# 1_MCU_and_BLE.net
KiCad netlist of a schematic drawn in Altium Designer
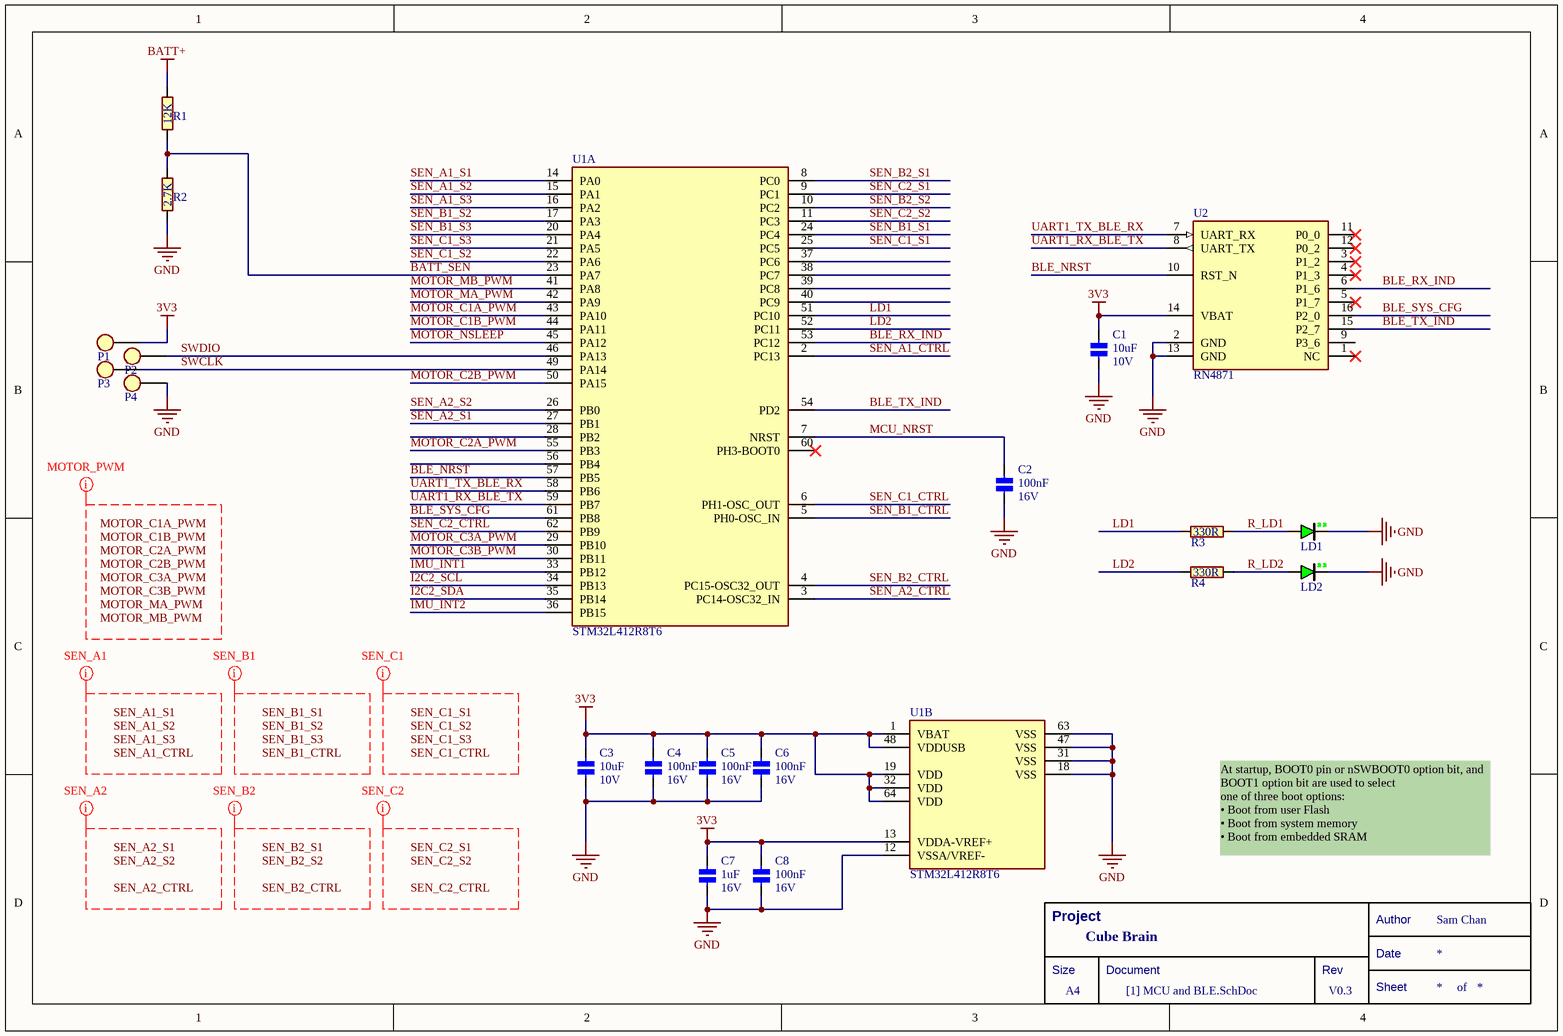
[diagram p0: [1] MCU and BLE.SchDoc]

(export (version "E")
  (design (tool "Eeschema 10.0.6"))
  (components
    (comp (ref "C1")
      (value "10uF")
      (footprint "CAPC0402X05N")
      (description "CAP CER 10UF 10V X5R 0402")
      (fields
        (field (name "MANUFACTURER") "Murata Electronics")
        (field (name "MANUFACTURER PART NUMBER") "GRM155R61A106ME44D")
        (field (name "CAPACITANCE") "10uF")
        (field (name "VOLTAGE - RATED") "10V")
      )
      (libsource (lib "Cube Library") (part "CER 10UF 10V"))
    )
    (comp (ref "C2")
      (value "100nF")
      (footprint "CAPC0402X05N")
      (description "CAP CER 0.1UF 16V X7R 0402")
      (fields
        (field (name "MANUFACTURER") "Samsung Electro-Mechanics")
        (field (name "MANUFACTURER PART NUMBER") "CL05B104KO5NNNC")
        (field (name "CAPACITANCE") "100nF")
        (field (name "VOLTAGE - RATED") "16V")
      )
      (libsource (lib "Cube Library") (part "CER 100NF 16V"))
    )
    (comp (ref "C3")
      (value "10uF")
      (footprint "CAPC0402X05N")
      (description "CAP CER 10UF 10V X5R 0402")
      (fields
        (field (name "MANUFACTURER") "Murata Electronics")
        (field (name "MANUFACTURER PART NUMBER") "GRM155R61A106ME44D")
        (field (name "CAPACITANCE") "10uF")
        (field (name "VOLTAGE - RATED") "10V")
      )
      (libsource (lib "Cube Library") (part "CER 10UF 10V"))
    )
    (comp (ref "C4")
      (value "100nF")
      (footprint "CAPC0402X05N")
      (description "CAP CER 0.1UF 16V X7R 0402")
      (fields
        (field (name "MANUFACTURER") "Samsung Electro-Mechanics")
        (field (name "MANUFACTURER PART NUMBER") "CL05B104KO5NNNC")
        (field (name "CAPACITANCE") "100nF")
        (field (name "VOLTAGE - RATED") "16V")
      )
      (libsource (lib "Cube Library") (part "CER 100NF 16V"))
    )
    (comp (ref "C5")
      (value "100nF")
      (footprint "CAPC0402X05N")
      (description "CAP CER 0.1UF 16V X7R 0402")
      (fields
        (field (name "MANUFACTURER") "Samsung Electro-Mechanics")
        (field (name "MANUFACTURER PART NUMBER") "CL05B104KO5NNNC")
        (field (name "CAPACITANCE") "100nF")
        (field (name "VOLTAGE - RATED") "16V")
      )
      (libsource (lib "Cube Library") (part "CER 100NF 16V"))
    )
    (comp (ref "C6")
      (value "100nF")
      (footprint "CAPC0402X05N")
      (description "CAP CER 0.1UF 16V X7R 0402")
      (fields
        (field (name "MANUFACTURER") "Samsung Electro-Mechanics")
        (field (name "MANUFACTURER PART NUMBER") "CL05B104KO5NNNC")
        (field (name "CAPACITANCE") "100nF")
        (field (name "VOLTAGE - RATED") "16V")
      )
      (libsource (lib "Cube Library") (part "CER 100NF 16V"))
    )
    (comp (ref "C7")
      (value "1uF")
      (footprint "CAPC0402X05N")
      (description "CAP CER 1UF 16V X5R 0402")
      (fields
        (field (name "MANUFACTURER") "Samsung Electro-Mechanics")
        (field (name "MANUFACTURER PART NUMBER") "CL05A105KO5NNNC")
        (field (name "CAPACITANCE") "1uF")
        (field (name "VOLTAGE - RATED") "16V")
      )
      (libsource (lib "Cube Library") (part "CER 1UF 16V"))
    )
    (comp (ref "C8")
      (value "100nF")
      (footprint "CAPC0402X05N")
      (description "CAP CER 0.1UF 16V X7R 0402")
      (fields
        (field (name "MANUFACTURER") "Samsung Electro-Mechanics")
        (field (name "MANUFACTURER PART NUMBER") "CL05B104KO5NNNC")
        (field (name "CAPACITANCE") "100nF")
        (field (name "VOLTAGE - RATED") "16V")
      )
      (libsource (lib "Cube Library") (part "CER 100NF 16V"))
    )
    (comp (ref "LD1")
      (value "Green")
      (footprint "LEDM0603X08N_GREEN")
      (description "LED GREEN CLEAR CHIP SMD")
      (fields
        (field (name "MANUFACTURER") "Lite-On Inc.")
        (field (name "MANUFACTURER PART NUMBER") "LTST-C190KGKT")
      )
      (libsource (lib "Cube Library") (part "LED 0603 GREEN"))
    )
    (comp (ref "LD2")
      (value "Green")
      (footprint "LEDM0603X08N_GREEN")
      (description "LED GREEN CLEAR CHIP SMD")
      (fields
        (field (name "MANUFACTURER") "Lite-On Inc.")
        (field (name "MANUFACTURER PART NUMBER") "LTST-C190KGKT")
      )
      (libsource (lib "Cube Library") (part "LED 0603 GREEN"))
    )
    (comp (ref "P1")
      (value "PAD_3")
      (footprint "Cube:PAD_ROUND_1MM")
      (description "a Round Pad 1mm")
      (libsource (lib "Cube") (part "PAD_3"))
    )
    (comp (ref "P2")
      (value "PAD_3")
      (footprint "Cube:PAD_ROUND_1MM")
      (description "a Round Pad 1mm")
      (libsource (lib "Cube") (part "PAD_3"))
    )
    (comp (ref "P3")
      (value "PAD_3")
      (footprint "Cube:PAD_ROUND_1MM")
      (description "a Round Pad 1mm")
      (libsource (lib "Cube") (part "PAD_3"))
    )
    (comp (ref "P4")
      (value "PAD_3")
      (footprint "Cube:PAD_ROUND_1MM")
      (description "a Round Pad 1mm")
      (libsource (lib "Cube") (part "PAD_3"))
    )
    (comp (ref "R1")
      (value "12K")
      (footprint "RESC0402X04N")
      (description "RES SMD 12K OHM 1% 1/16W 0402")
      (fields
        (field (name "MANUFACTURER") "YAGEO")
        (field (name "MANUFACTURER PART NUMBER") "RC0402FR-0712KL")
        (field (name "RESISTANCE") "12K")
      )
      (libsource (lib "Cube Library") (part "RES 12K"))
    )
    (comp (ref "R2")
      (value "2.7K")
      (footprint "RESC0402X04N")
      (description "RES SMD 2.7K OHM 1% 1/16W 0402")
      (fields
        (field (name "MANUFACTURER") "YAGEO")
        (field (name "MANUFACTURER PART NUMBER") "AC0402FR-072K7L")
        (field (name "RESISTANCE") "2.7K")
      )
      (libsource (lib "Cube Library") (part "RES 2.7K"))
    )
    (comp (ref "R3")
      (value "330R")
      (footprint "RESC0402X04N")
      (description "RES SMD 330R OHM 1% 1/16W 0402")
      (fields
        (field (name "MANUFACTURER") "YAGEO")
        (field (name "MANUFACTURER PART NUMBER") "RC0402FR-07330RL")
        (field (name "RESISTANCE") "330R")
      )
      (libsource (lib "Cube Library") (part "RES 330R"))
    )
    (comp (ref "R4")
      (value "330R")
      (footprint "RESC0402X04N")
      (description "RES SMD 330R OHM 1% 1/16W 0402")
      (fields
        (field (name "MANUFACTURER") "YAGEO")
        (field (name "MANUFACTURER PART NUMBER") "RC0402FR-07330RL")
        (field (name "RESISTANCE") "330R")
      )
      (libsource (lib "Cube Library") (part "RES 330R"))
    )
    (comp (ref "U1")
      (value "STM32L412R8T6")
      (footprint "STM32L412R")
      (description "ARM® Cortex®-M4 STM32L4 Microcontroller IC 32-Bit 80MHz 64KB (64K x 8) FLASH 64-LQFP (10x10)")
      (fields (field (name "MANUFACTURER") "STMicroelectronics"))
      (libsource (lib "Cube Library") (part "STM32L412R8T6"))
    )
    (comp (ref "U2")
      (value "RN4871")
      (footprint "RN4871")
      (description "Bluetooth Bluetooth v5.0 Transceiver Module 2.4GHz Integrated, Chip Surface Mount")
      (fields
        (field (name "MANUFACTURER") "Microchip Technology")
        (field (name "MANUFACTURER PART NUMBER") "RN4871-I/RM130")
      )
      (libsource (lib "Cube Library") (part "RN4871"))
    )
  )
  (nets
    (net (code "1") (name "/BATT_SEN") (class "Default")
      (node (ref "R1") (pin "1") (pinfunction "1_1") (pintype "passive"))
      (node (ref "R2") (pin "2") (pinfunction "2_2") (pintype "passive"))
      (node (ref "U1") (pin "23") (pinfunction "PA7_23") (pintype "passive"))
    )
    (net (code "2") (name "/BLE_NRST") (class "Default")
      (node (ref "U1") (pin "57") (pinfunction "PB5_57") (pintype "passive"))
      (node (ref "U2") (pin "10") (pinfunction "RST_N_10") (pintype "passive"))
    )
    (net (code "3") (name "/BLE_RX_IND") (class "Default")
      (node (ref "U1") (pin "53") (pinfunction "PC12_53") (pintype "passive"))
      (node (ref "U2") (pin "6") (pinfunction "P1_6_6") (pintype "passive"))
    )
    (net (code "4") (name "/BLE_SYS_CFG") (class "Default")
      (node (ref "U1") (pin "61") (pinfunction "PB8_61") (pintype "passive"))
      (node (ref "U2") (pin "16") (pinfunction "P2_0_16") (pintype "passive"))
    )
    (net (code "5") (name "/BLE_TX_IND") (class "Default")
      (node (ref "U1") (pin "54") (pinfunction "PD2_54") (pintype "passive"))
      (node (ref "U2") (pin "15") (pinfunction "P2_7_15") (pintype "passive"))
    )
    (net (code "6") (name "/I2C2_SCL") (class "Default")
      (node (ref "U1") (pin "34") (pinfunction "PB13_34") (pintype "passive"))
    )
    (net (code "7") (name "/I2C2_SDA") (class "Default")
      (node (ref "U1") (pin "35") (pinfunction "PB14_35") (pintype "passive"))
    )
    (net (code "8") (name "/IMU_INT1") (class "Default")
      (node (ref "U1") (pin "33") (pinfunction "PB12_33") (pintype "passive"))
    )
    (net (code "9") (name "/IMU_INT2") (class "Default")
      (node (ref "U1") (pin "36") (pinfunction "PB15_36") (pintype "passive"))
    )
    (net (code "10") (name "/LD1") (class "Default")
      (node (ref "R3") (pin "1") (pinfunction "1_1") (pintype "passive"))
      (node (ref "U1") (pin "51") (pinfunction "PC10_51") (pintype "passive"))
    )
    (net (code "11") (name "/LD2") (class "Default")
      (node (ref "R4") (pin "1") (pinfunction "1_1") (pintype "passive"))
      (node (ref "U1") (pin "52") (pinfunction "PC11_52") (pintype "passive"))
    )
    (net (code "12") (name "/MCU_NRST") (class "Default")
      (node (ref "C2") (pin "1") (pinfunction "1_1") (pintype "passive"))
      (node (ref "U1") (pin "7") (pinfunction "NRST_7") (pintype "passive"))
    )
    (net (code "13") (name "/MOTOR_C1A_PWM") (class "Default")
      (node (ref "U1") (pin "43") (pinfunction "PA10_43") (pintype "passive"))
    )
    (net (code "14") (name "/MOTOR_C1B_PWM") (class "Default")
      (node (ref "U1") (pin "44") (pinfunction "PA11_44") (pintype "passive"))
    )
    (net (code "15") (name "/MOTOR_C2A_PWM") (class "Default")
      (node (ref "U1") (pin "55") (pinfunction "PB3_55") (pintype "passive"))
    )
    (net (code "16") (name "/MOTOR_C2B_PWM") (class "Default")
      (node (ref "U1") (pin "50") (pinfunction "PA15_50") (pintype "passive"))
    )
    (net (code "17") (name "/MOTOR_C3A_PWM") (class "Default")
      (node (ref "U1") (pin "29") (pinfunction "PB10_29") (pintype "passive"))
    )
    (net (code "18") (name "/MOTOR_C3B_PWM") (class "Default")
      (node (ref "U1") (pin "30") (pinfunction "PB11_30") (pintype "passive"))
    )
    (net (code "19") (name "/MOTOR_MA_PWM") (class "Default")
      (node (ref "U1") (pin "42") (pinfunction "PA9_42") (pintype "passive"))
    )
    (net (code "20") (name "/MOTOR_MB_PWM") (class "Default")
      (node (ref "U1") (pin "41") (pinfunction "PA8_41") (pintype "passive"))
    )
    (net (code "21") (name "/MOTOR_NSLEEP") (class "Default")
      (node (ref "U1") (pin "45") (pinfunction "PA12_45") (pintype "passive"))
    )
    (net (code "22") (name "/R_LD1") (class "Default")
      (node (ref "LD1") (pin "1") (pinfunction "1_1") (pintype "passive"))
      (node (ref "R3") (pin "2") (pinfunction "2_2") (pintype "passive"))
    )
    (net (code "23") (name "/R_LD2") (class "Default")
      (node (ref "LD2") (pin "1") (pinfunction "1_1") (pintype "passive"))
      (node (ref "R4") (pin "2") (pinfunction "2_2") (pintype "passive"))
    )
    (net (code "24") (name "/SEN_A1_CTRL") (class "Default")
      (node (ref "U1") (pin "2") (pinfunction "PC13_2") (pintype "passive"))
    )
    (net (code "25") (name "/SEN_A1_S1") (class "Default")
      (node (ref "U1") (pin "14") (pinfunction "PA0_14") (pintype "passive"))
    )
    (net (code "26") (name "/SEN_A1_S2") (class "Default")
      (node (ref "U1") (pin "15") (pinfunction "PA1_15") (pintype "passive"))
    )
    (net (code "27") (name "/SEN_A1_S3") (class "Default")
      (node (ref "U1") (pin "16") (pinfunction "PA2_16") (pintype "passive"))
    )
    (net (code "28") (name "/SEN_A2_CTRL") (class "Default")
      (node (ref "U1") (pin "3") (pinfunction "PC14-OSC32_IN_3") (pintype "passive"))
    )
    (net (code "29") (name "/SEN_A2_S1") (class "Default")
      (node (ref "U1") (pin "27") (pinfunction "PB1_27") (pintype "passive"))
    )
    (net (code "30") (name "/SEN_A2_S2") (class "Default")
      (node (ref "U1") (pin "26") (pinfunction "PB0_26") (pintype "passive"))
    )
    (net (code "31") (name "/SEN_B1_CTRL") (class "Default")
      (node (ref "U1") (pin "5") (pinfunction "PH0-OSC_IN_5") (pintype "passive"))
    )
    (net (code "32") (name "/SEN_B1_S1") (class "Default")
      (node (ref "U1") (pin "24") (pinfunction "PC4_24") (pintype "passive"))
    )
    (net (code "33") (name "/SEN_B1_S2") (class "Default")
      (node (ref "U1") (pin "17") (pinfunction "PA3_17") (pintype "passive"))
    )
    (net (code "34") (name "/SEN_B1_S3") (class "Default")
      (node (ref "U1") (pin "20") (pinfunction "PA4_20") (pintype "passive"))
    )
    (net (code "35") (name "/SEN_B2_CTRL") (class "Default")
      (node (ref "U1") (pin "4") (pinfunction "PC15-OSC32_OUT_4") (pintype "passive"))
    )
    (net (code "36") (name "/SEN_B2_S1") (class "Default")
      (node (ref "U1") (pin "8") (pinfunction "PC0_8") (pintype "passive"))
    )
    (net (code "37") (name "/SEN_B2_S2") (class "Default")
      (node (ref "U1") (pin "10") (pinfunction "PC2_10") (pintype "passive"))
    )
    (net (code "38") (name "/SEN_C1_CTRL") (class "Default")
      (node (ref "U1") (pin "6") (pinfunction "PH1-OSC_OUT_6") (pintype "passive"))
    )
    (net (code "39") (name "/SEN_C1_S1") (class "Default")
      (node (ref "U1") (pin "25") (pinfunction "PC5_25") (pintype "passive"))
    )
    (net (code "40") (name "/SEN_C1_S2") (class "Default")
      (node (ref "U1") (pin "22") (pinfunction "PA6_22") (pintype "passive"))
    )
    (net (code "41") (name "/SEN_C1_S3") (class "Default")
      (node (ref "U1") (pin "21") (pinfunction "PA5_21") (pintype "passive"))
    )
    (net (code "42") (name "/SEN_C2_CTRL") (class "Default")
      (node (ref "U1") (pin "62") (pinfunction "PB9_62") (pintype "passive"))
    )
    (net (code "43") (name "/SEN_C2_S1") (class "Default")
      (node (ref "U1") (pin "9") (pinfunction "PC1_9") (pintype "passive"))
    )
    (net (code "44") (name "/SEN_C2_S2") (class "Default")
      (node (ref "U1") (pin "11") (pinfunction "PC3_11") (pintype "passive"))
    )
    (net (code "45") (name "/SWCLK") (class "Default")
      (node (ref "P3") (pin "1") (pinfunction "1_1") (pintype "passive"))
      (node (ref "U1") (pin "49") (pinfunction "PA14_49") (pintype "passive"))
    )
    (net (code "46") (name "/SWDIO") (class "Default")
      (node (ref "P2") (pin "1") (pinfunction "1_1") (pintype "passive"))
      (node (ref "U1") (pin "46") (pinfunction "PA13_46") (pintype "passive"))
    )
    (net (code "47") (name "/UART1_RX_BLE_TX") (class "Default")
      (node (ref "U1") (pin "59") (pinfunction "PB7_59") (pintype "passive"))
      (node (ref "U2") (pin "8") (pinfunction "UART_TX_8") (pintype "output"))
    )
    (net (code "48") (name "/UART1_TX_BLE_RX") (class "Default")
      (node (ref "U1") (pin "58") (pinfunction "PB6_58") (pintype "passive"))
      (node (ref "U2") (pin "7") (pinfunction "UART_RX_7") (pintype "input"))
    )
    (net (code "49") (name "3V3") (class "Default")
      (node (ref "C1") (pin "1") (pinfunction "1_1") (pintype "passive"))
      (node (ref "C3") (pin "1") (pinfunction "1_1") (pintype "passive"))
      (node (ref "C4") (pin "1") (pinfunction "1_1") (pintype "passive"))
      (node (ref "C5") (pin "1") (pinfunction "1_1") (pintype "passive"))
      (node (ref "C6") (pin "1") (pinfunction "1_1") (pintype "passive"))
      (node (ref "C7") (pin "1") (pinfunction "1_1") (pintype "passive"))
      (node (ref "C8") (pin "1") (pinfunction "1_1") (pintype "passive"))
      (node (ref "P1") (pin "1") (pinfunction "1_1") (pintype "passive"))
      (node (ref "U1") (pin "1") (pinfunction "VBAT_1") (pintype "passive"))
      (node (ref "U1") (pin "13") (pinfunction "VDDA-VREF+_13") (pintype "passive"))
      (node (ref "U1") (pin "19") (pinfunction "VDD_19") (pintype "passive"))
      (node (ref "U1") (pin "32") (pinfunction "VDD_32") (pintype "passive"))
      (node (ref "U1") (pin "48") (pinfunction "VDDUSB_48") (pintype "passive"))
      (node (ref "U1") (pin "64") (pinfunction "VDD_64") (pintype "passive"))
      (node (ref "U2") (pin "14") (pinfunction "VBAT_14") (pintype "passive"))
    )
    (net (code "50") (name "BATT+") (class "Default")
      (node (ref "R1") (pin "2") (pinfunction "2_2") (pintype "passive"))
    )
    (net (code "51") (name "GND") (class "Default")
      (node (ref "C1") (pin "2") (pinfunction "2_2") (pintype "passive"))
      (node (ref "C2") (pin "2") (pinfunction "2_2") (pintype "passive"))
      (node (ref "C3") (pin "2") (pinfunction "2_2") (pintype "passive"))
      (node (ref "C4") (pin "2") (pinfunction "2_2") (pintype "passive"))
      (node (ref "C5") (pin "2") (pinfunction "2_2") (pintype "passive"))
      (node (ref "C6") (pin "2") (pinfunction "2_2") (pintype "passive"))
      (node (ref "C7") (pin "2") (pinfunction "2_2") (pintype "passive"))
      (node (ref "C8") (pin "2") (pinfunction "2_2") (pintype "passive"))
      (node (ref "LD1") (pin "2") (pinfunction "2_2") (pintype "passive"))
      (node (ref "LD2") (pin "2") (pinfunction "2_2") (pintype "passive"))
      (node (ref "P4") (pin "1") (pinfunction "1_1") (pintype "passive"))
      (node (ref "R2") (pin "1") (pinfunction "1_1") (pintype "passive"))
      (node (ref "U1") (pin "12") (pinfunction "VSSA/VREF-_12") (pintype "passive"))
      (node (ref "U1") (pin "18") (pinfunction "VSS_18") (pintype "passive"))
      (node (ref "U1") (pin "31") (pinfunction "VSS_31") (pintype "passive"))
      (node (ref "U1") (pin "47") (pinfunction "VSS_47") (pintype "passive"))
      (node (ref "U1") (pin "63") (pinfunction "VSS_63") (pintype "passive"))
      (node (ref "U2") (pin "13") (pinfunction "GND_13") (pintype "passive"))
      (node (ref "U2") (pin "2") (pinfunction "GND_2") (pintype "passive"))
    )
    (net (code "52") (name "unconnected-(U1A-PB2-Pad28)") (class "Default")
      (node (ref "U1") (pin "28") (pinfunction "PB2_28") (pintype "passive"))
    )
    (net (code "53") (name "unconnected-(U1A-PB4-Pad56)") (class "Default")
      (node (ref "U1") (pin "56") (pinfunction "PB4_56") (pintype "passive"))
    )
    (net (code "54") (name "unconnected-(U1A-PC6-Pad37)") (class "Default")
      (node (ref "U1") (pin "37") (pinfunction "PC6_37") (pintype "passive"))
    )
    (net (code "55") (name "unconnected-(U1A-PC7-Pad38)") (class "Default")
      (node (ref "U1") (pin "38") (pinfunction "PC7_38") (pintype "passive"))
    )
    (net (code "56") (name "unconnected-(U1A-PC8-Pad39)") (class "Default")
      (node (ref "U1") (pin "39") (pinfunction "PC8_39") (pintype "passive"))
    )
    (net (code "57") (name "unconnected-(U1A-PC9-Pad40)") (class "Default")
      (node (ref "U1") (pin "40") (pinfunction "PC9_40") (pintype "passive"))
    )
    (net (code "58") (name "unconnected-(U1A-PH3-BOOT0-Pad60)") (class "Default")
      (node (ref "U1") (pin "60") (pinfunction "PH3-BOOT0_60") (pintype "passive+no_connect"))
    )
    (net (code "59") (name "unconnected-(U2-NC-Pad1)") (class "Default")
      (node (ref "U2") (pin "1") (pinfunction "NC_1") (pintype "passive+no_connect"))
    )
    (net (code "60") (name "unconnected-(U2-P0_0-Pad11)") (class "Default")
      (node (ref "U2") (pin "11") (pinfunction "P0_0_11") (pintype "passive+no_connect"))
    )
    (net (code "61") (name "unconnected-(U2-P0_2-Pad12)") (class "Default")
      (node (ref "U2") (pin "12") (pinfunction "P0_2_12") (pintype "passive+no_connect"))
    )
    (net (code "62") (name "unconnected-(U2-P1_2-Pad3)") (class "Default")
      (node (ref "U2") (pin "3") (pinfunction "P1_2_3") (pintype "passive+no_connect"))
    )
    (net (code "63") (name "unconnected-(U2-P1_3-Pad4)") (class "Default")
      (node (ref "U2") (pin "4") (pinfunction "P1_3_4") (pintype "passive+no_connect"))
    )
    (net (code "64") (name "unconnected-(U2-P1_7-Pad5)") (class "Default")
      (node (ref "U2") (pin "5") (pinfunction "P1_7_5") (pintype "passive+no_connect"))
    )
    (net (code "65") (name "unconnected-(U2-P3_6-Pad9)") (class "Default")
      (node (ref "U2") (pin "9") (pinfunction "P3_6_9") (pintype "passive"))
    )
  )
)
